# ADC.net
KiCad netlist of a schematic drawn in Altium Designer
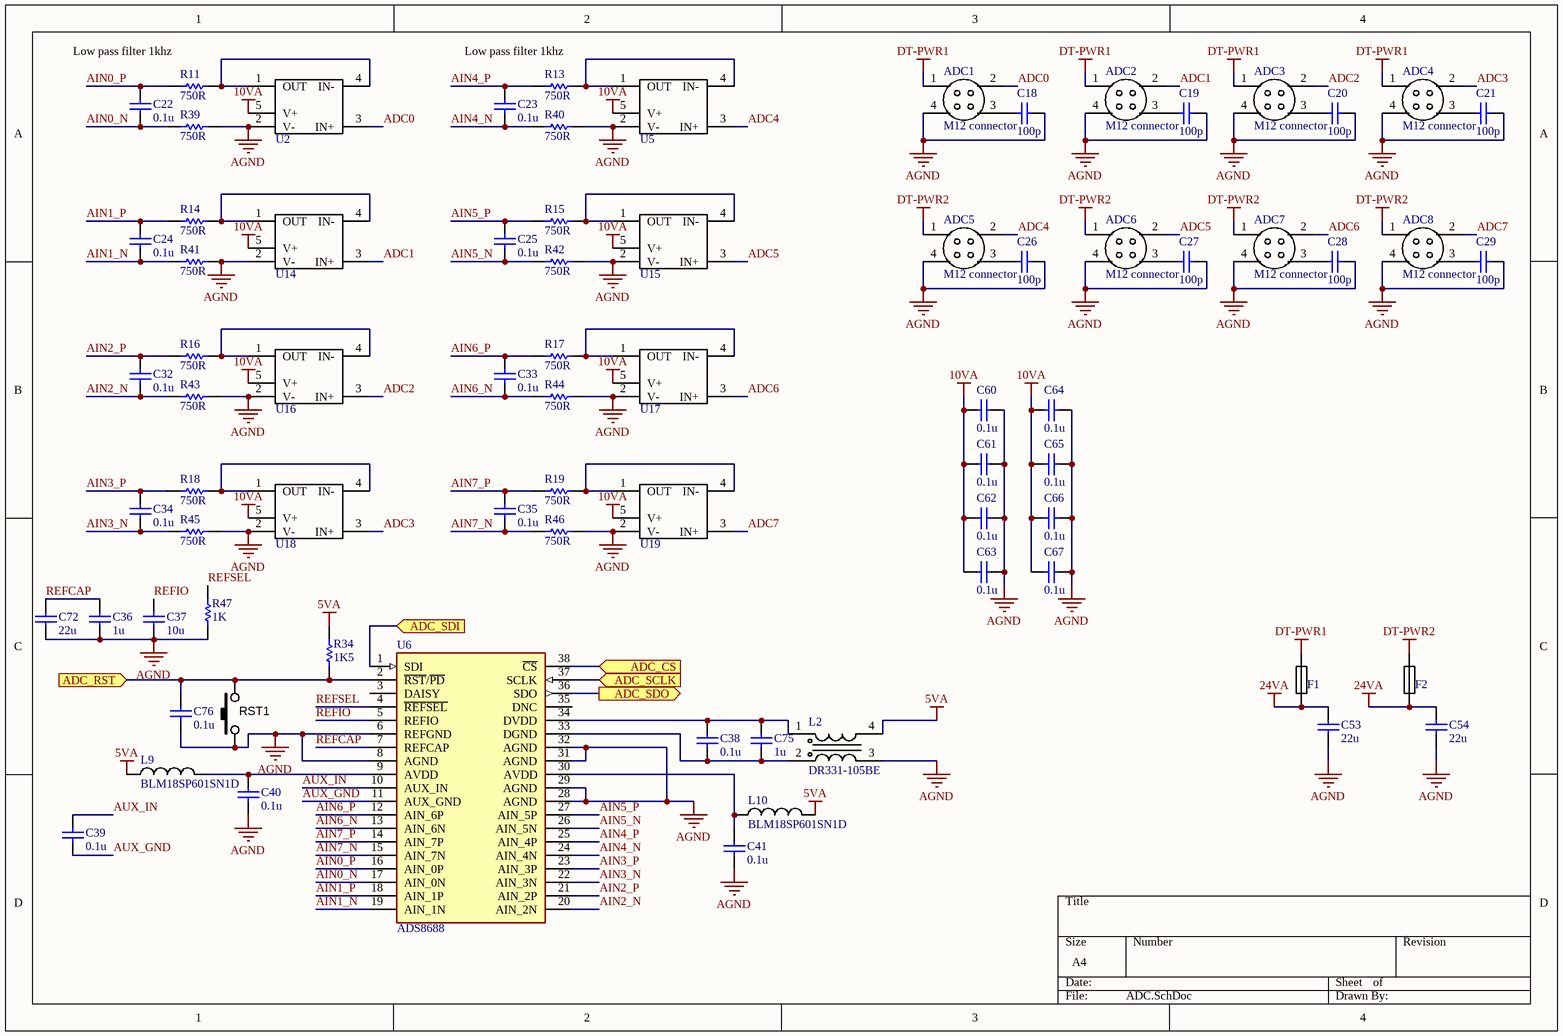
[diagram p0: ADC.SchDoc]

(export (version "E")
  (design (tool "Eeschema 10.0.6"))
  (components
    (comp (ref "ADC1")
      (value "M12 connector")
      (footprint "GX12_PCB_Mount")
      (description "M12 connect with 4 pin, current 4A per terminal")
      (libsource (lib "IOBoard") (part "M12_connector"))
    )
    (comp (ref "ADC2")
      (value "M12 connector")
      (footprint "GX12_PCB_Mount")
      (description "M12 connect with 4 pin, current 4A per terminal")
      (libsource (lib "IOBoard") (part "M12_connector"))
    )
    (comp (ref "ADC3")
      (value "M12 connector")
      (footprint "GX12_PCB_Mount")
      (description "M12 connect with 4 pin, current 4A per terminal")
      (libsource (lib "IOBoard") (part "M12_connector"))
    )
    (comp (ref "ADC4")
      (value "M12 connector")
      (footprint "GX12_PCB_Mount")
      (description "M12 connect with 4 pin, current 4A per terminal")
      (libsource (lib "IOBoard") (part "M12_connector"))
    )
    (comp (ref "ADC5")
      (value "M12 connector")
      (footprint "GX12_PCB_Mount")
      (description "M12 connect with 4 pin, current 4A per terminal")
      (libsource (lib "IOBoard") (part "M12_connector"))
    )
    (comp (ref "ADC6")
      (value "M12 connector")
      (footprint "GX12_PCB_Mount")
      (description "M12 connect with 4 pin, current 4A per terminal")
      (libsource (lib "IOBoard") (part "M12_connector"))
    )
    (comp (ref "ADC7")
      (value "M12 connector")
      (footprint "GX12_PCB_Mount")
      (description "M12 connect with 4 pin, current 4A per terminal")
      (libsource (lib "IOBoard") (part "M12_connector"))
    )
    (comp (ref "ADC8")
      (value "M12 connector")
      (footprint "GX12_PCB_Mount")
      (description "M12 connect with 4 pin, current 4A per terminal")
      (libsource (lib "IOBoard") (part "M12_connector"))
    )
    (comp (ref "C18")
      (value "100p")
      (footprint "CAPC1608X90N")
      (description "Capacitor")
      (fields (field (name "Comment") "Cap") (field (name "PUBLISHER") "Altium Limited"))
      (libsource (lib "IOBoard_Low") (part "Cap"))
    )
    (comp (ref "C19")
      (value "100p")
      (footprint "CAPC1608X90N")
      (description "Capacitor")
      (fields (field (name "Comment") "Cap") (field (name "PUBLISHER") "Altium Limited"))
      (libsource (lib "IOBoard_Low") (part "Cap"))
    )
    (comp (ref "C20")
      (value "100p")
      (footprint "CAPC1608X90N")
      (description "Capacitor")
      (fields (field (name "Comment") "Cap") (field (name "PUBLISHER") "Altium Limited"))
      (libsource (lib "IOBoard_Low") (part "Cap"))
    )
    (comp (ref "C21")
      (value "100p")
      (footprint "CAPC1608X90N")
      (description "Capacitor")
      (fields (field (name "Comment") "Cap") (field (name "PUBLISHER") "Altium Limited"))
      (libsource (lib "IOBoard_Low") (part "Cap"))
    )
    (comp (ref "C22")
      (value "0.1u")
      (footprint "CAPC1608X90N")
      (description "Capacitor")
      (fields (field (name "Comment") "Cap") (field (name "PUBLISHER") "Altium Limited"))
      (libsource (lib "IOBoard_Low") (part "Cap"))
    )
    (comp (ref "C23")
      (value "0.1u")
      (footprint "CAPC1608X90N")
      (description "Capacitor")
      (fields (field (name "Comment") "Cap") (field (name "PUBLISHER") "Altium Limited"))
      (libsource (lib "IOBoard_Low") (part "Cap"))
    )
    (comp (ref "C24")
      (value "0.1u")
      (footprint "CAPC1608X90N")
      (description "Capacitor")
      (fields (field (name "Comment") "Cap") (field (name "PUBLISHER") "Altium Limited"))
      (libsource (lib "IOBoard_Low") (part "Cap"))
    )
    (comp (ref "C25")
      (value "0.1u")
      (footprint "CAPC1608X90N")
      (description "Capacitor")
      (fields (field (name "Comment") "Cap") (field (name "PUBLISHER") "Altium Limited"))
      (libsource (lib "IOBoard_Low") (part "Cap"))
    )
    (comp (ref "C26")
      (value "100p")
      (footprint "CAPC1608X90N")
      (description "Capacitor")
      (fields (field (name "Comment") "Cap") (field (name "PUBLISHER") "Altium Limited"))
      (libsource (lib "IOBoard_Low") (part "Cap"))
    )
    (comp (ref "C27")
      (value "100p")
      (footprint "CAPC1608X90N")
      (description "Capacitor")
      (fields (field (name "Comment") "Cap") (field (name "PUBLISHER") "Altium Limited"))
      (libsource (lib "IOBoard_Low") (part "Cap"))
    )
    (comp (ref "C28")
      (value "100p")
      (footprint "CAPC1608X90N")
      (description "Capacitor")
      (fields (field (name "Comment") "Cap") (field (name "PUBLISHER") "Altium Limited"))
      (libsource (lib "IOBoard_Low") (part "Cap"))
    )
    (comp (ref "C29")
      (value "100p")
      (footprint "CAPC1608X90N")
      (description "Capacitor")
      (fields (field (name "Comment") "Cap") (field (name "PUBLISHER") "Altium Limited"))
      (libsource (lib "IOBoard_Low") (part "Cap"))
    )
    (comp (ref "C32")
      (value "0.1u")
      (footprint "CAPC1608X90N")
      (description "Capacitor")
      (fields (field (name "Comment") "Cap") (field (name "PUBLISHER") "Altium Limited"))
      (libsource (lib "IOBoard_Low") (part "Cap"))
    )
    (comp (ref "C33")
      (value "0.1u")
      (footprint "CAPC1608X90N")
      (description "Capacitor")
      (fields (field (name "Comment") "Cap") (field (name "PUBLISHER") "Altium Limited"))
      (libsource (lib "IOBoard_Low") (part "Cap"))
    )
    (comp (ref "C34")
      (value "0.1u")
      (footprint "CAPC1608X90N")
      (description "Capacitor")
      (fields (field (name "Comment") "Cap") (field (name "PUBLISHER") "Altium Limited"))
      (libsource (lib "IOBoard_Low") (part "Cap"))
    )
    (comp (ref "C35")
      (value "0.1u")
      (footprint "CAPC1608X90N")
      (description "Capacitor")
      (fields (field (name "Comment") "Cap") (field (name "PUBLISHER") "Altium Limited"))
      (libsource (lib "IOBoard_Low") (part "Cap"))
    )
    (comp (ref "C36")
      (value "1u")
      (footprint "CAPC1608X90N")
      (description "Capacitor")
      (fields (field (name "Comment") "Cap") (field (name "PUBLISHER") "Altium Limited"))
      (libsource (lib "IOBoard_Low") (part "Cap"))
    )
    (comp (ref "C37")
      (value "10u")
      (footprint "CAPC1608X90N")
      (description "Capacitor")
      (fields (field (name "Comment") "Cap") (field (name "PUBLISHER") "Altium Limited"))
      (libsource (lib "IOBoard_Low") (part "Cap"))
    )
    (comp (ref "C38")
      (value "0.1u")
      (footprint "CAPC1608X90N")
      (description "Capacitor")
      (fields (field (name "Comment") "Cap") (field (name "PUBLISHER") "Altium Limited"))
      (libsource (lib "IOBoard_Low") (part "Cap"))
    )
    (comp (ref "C39")
      (value "0.1u")
      (footprint "CAPC1608X90N")
      (description "Capacitor")
      (fields (field (name "Comment") "Cap") (field (name "PUBLISHER") "Altium Limited"))
      (libsource (lib "IOBoard_Low") (part "Cap"))
    )
    (comp (ref "C40")
      (value "0.1u")
      (footprint "CAPC1608X90N")
      (description "Capacitor")
      (fields (field (name "Comment") "Cap") (field (name "PUBLISHER") "Altium Limited"))
      (libsource (lib "IOBoard_Low") (part "Cap"))
    )
    (comp (ref "C41")
      (value "0.1u")
      (footprint "CAPC1608X90N")
      (description "Capacitor")
      (fields (field (name "Comment") "Cap") (field (name "PUBLISHER") "Altium Limited"))
      (libsource (lib "IOBoard_Low") (part "Cap"))
    )
    (comp (ref "C53")
      (value "22u")
      (footprint "CAPC2012X135N")
      (description "Capacitor")
      (fields (field (name "Comment") "Cap") (field (name "PUBLISHER") "Altium Limited"))
      (libsource (lib "IOBoard_Low") (part "Cap"))
    )
    (comp (ref "C54")
      (value "22u")
      (footprint "CAPC2012X135N")
      (description "Capacitor")
      (fields (field (name "Comment") "Cap") (field (name "PUBLISHER") "Altium Limited"))
      (libsource (lib "IOBoard_Low") (part "Cap"))
    )
    (comp (ref "C60")
      (value "0.1u")
      (footprint "CAPC1608X90N")
      (description "Capacitor")
      (fields (field (name "Comment") "Cap") (field (name "PUBLISHER") "Altium Limited"))
      (libsource (lib "IOBoard_Low") (part "Cap"))
    )
    (comp (ref "C61")
      (value "0.1u")
      (footprint "CAPC1608X90N")
      (description "Capacitor")
      (fields (field (name "Comment") "Cap") (field (name "PUBLISHER") "Altium Limited"))
      (libsource (lib "IOBoard_Low") (part "Cap"))
    )
    (comp (ref "C62")
      (value "0.1u")
      (footprint "CAPC1608X90N")
      (description "Capacitor")
      (fields (field (name "Comment") "Cap") (field (name "PUBLISHER") "Altium Limited"))
      (libsource (lib "IOBoard_Low") (part "Cap"))
    )
    (comp (ref "C63")
      (value "0.1u")
      (footprint "CAPC1608X90N")
      (description "Capacitor")
      (fields (field (name "Comment") "Cap") (field (name "PUBLISHER") "Altium Limited"))
      (libsource (lib "IOBoard_Low") (part "Cap"))
    )
    (comp (ref "C64")
      (value "0.1u")
      (footprint "CAPC1608X90N")
      (description "Capacitor")
      (fields (field (name "Comment") "Cap") (field (name "PUBLISHER") "Altium Limited"))
      (libsource (lib "IOBoard_Low") (part "Cap"))
    )
    (comp (ref "C65")
      (value "0.1u")
      (footprint "CAPC1608X90N")
      (description "Capacitor")
      (fields (field (name "Comment") "Cap") (field (name "PUBLISHER") "Altium Limited"))
      (libsource (lib "IOBoard_Low") (part "Cap"))
    )
    (comp (ref "C66")
      (value "0.1u")
      (footprint "CAPC1608X90N")
      (description "Capacitor")
      (fields (field (name "Comment") "Cap") (field (name "PUBLISHER") "Altium Limited"))
      (libsource (lib "IOBoard_Low") (part "Cap"))
    )
    (comp (ref "C67")
      (value "0.1u")
      (footprint "CAPC1608X90N")
      (description "Capacitor")
      (fields (field (name "Comment") "Cap") (field (name "PUBLISHER") "Altium Limited"))
      (libsource (lib "IOBoard_Low") (part "Cap"))
    )
    (comp (ref "C72")
      (value "22u")
      (footprint "CAPC2012X135N")
      (description "Capacitor")
      (fields (field (name "Comment") "Cap") (field (name "PUBLISHER") "Altium Limited"))
      (libsource (lib "IOBoard_Low") (part "Cap"))
    )
    (comp (ref "C75")
      (value "1u")
      (footprint "CAPC1608X90N")
      (description "Capacitor")
      (fields (field (name "Comment") "Cap") (field (name "PUBLISHER") "Altium Limited"))
      (libsource (lib "IOBoard_Low") (part "Cap"))
    )
    (comp (ref "C76")
      (value "0.1u")
      (footprint "CAPC1608X90N")
      (description "Capacitor")
      (fields (field (name "Comment") "Cap") (field (name "PUBLISHER") "Altium Limited"))
      (libsource (lib "IOBoard_Low") (part "Cap"))
    )
    (comp (ref "F1")
      (value "MFU0805FF00500P100")
      (footprint "RESC2012X70N")
      (description "fuse 32V 0.5A")
      (libsource (lib "IOBoard") (part "FUSE_32V_500MA_0805"))
    )
    (comp (ref "F2")
      (value "MFU0805FF00500P100")
      (footprint "RESC2012X70N")
      (description "fuse 32V 0.5A")
      (libsource (lib "IOBoard") (part "FUSE_32V_500MA_0805"))
    )
    (comp (ref "L2")
      (value "DR331-105BE")
      (footprint "DR331-105BE")
      (description "Common mode choke 1mH 0.5A")
      (libsource (lib "IOBoard_Low") (part "DR331-105BE"))
    )
    (comp (ref "L9")
      (value "BLM18SP601SN1D")
      (footprint "INDC1608N")
      (description "Ferritebead 1.5A, max 600ohm resistance")
      (libsource (lib "IOBoard") (part "INC_BLM18SP601SN1D"))
    )
    (comp (ref "L10")
      (value "BLM18SP601SN1D")
      (footprint "INDC1608N")
      (description "Ferritebead 1.5A, max 600ohm resistance")
      (libsource (lib "IOBoard") (part "INC_BLM18SP601SN1D"))
    )
    (comp (ref "R11")
      (value "750R")
      (footprint "RESC1608X55N")
      (description "Resistor")
      (fields (field (name "Comment") "Res1") (field (name "PUBLISHER") "Altium Limited"))
      (libsource (lib "IOBoard_Low") (part "Res1"))
    )
    (comp (ref "R13")
      (value "750R")
      (footprint "RESC1608X55N")
      (description "Resistor")
      (fields (field (name "Comment") "Res1") (field (name "PUBLISHER") "Altium Limited"))
      (libsource (lib "IOBoard_Low") (part "Res1"))
    )
    (comp (ref "R14")
      (value "750R")
      (footprint "RESC1608X55N")
      (description "Resistor")
      (fields (field (name "Comment") "Res1") (field (name "PUBLISHER") "Altium Limited"))
      (libsource (lib "IOBoard_Low") (part "Res1"))
    )
    (comp (ref "R15")
      (value "750R")
      (footprint "RESC1608X55N")
      (description "Resistor")
      (fields (field (name "Comment") "Res1") (field (name "PUBLISHER") "Altium Limited"))
      (libsource (lib "IOBoard_Low") (part "Res1"))
    )
    (comp (ref "R16")
      (value "750R")
      (footprint "RESC1608X55N")
      (description "Resistor")
      (fields (field (name "Comment") "Res1") (field (name "PUBLISHER") "Altium Limited"))
      (libsource (lib "IOBoard_Low") (part "Res1"))
    )
    (comp (ref "R17")
      (value "750R")
      (footprint "RESC1608X55N")
      (description "Resistor")
      (fields (field (name "Comment") "Res1") (field (name "PUBLISHER") "Altium Limited"))
      (libsource (lib "IOBoard_Low") (part "Res1"))
    )
    (comp (ref "R18")
      (value "750R")
      (footprint "RESC1608X55N")
      (description "Resistor")
      (fields (field (name "Comment") "Res1") (field (name "PUBLISHER") "Altium Limited"))
      (libsource (lib "IOBoard_Low") (part "Res1"))
    )
    (comp (ref "R19")
      (value "750R")
      (footprint "RESC1608X55N")
      (description "Resistor")
      (fields (field (name "Comment") "Res1") (field (name "PUBLISHER") "Altium Limited"))
      (libsource (lib "IOBoard_Low") (part "Res1"))
    )
    (comp (ref "R34")
      (value "1K5")
      (footprint "RESC1608X55N")
      (description "Resistor")
      (fields (field (name "Comment") "Res1") (field (name "PUBLISHER") "Altium Limited"))
      (libsource (lib "IOBoard_Low") (part "Res1"))
    )
    (comp (ref "R39")
      (value "750R")
      (footprint "RESC1608X55N")
      (description "Resistor")
      (fields (field (name "Comment") "Res1") (field (name "PUBLISHER") "Altium Limited"))
      (libsource (lib "IOBoard_Low") (part "Res1"))
    )
    (comp (ref "R40")
      (value "750R")
      (footprint "RESC1608X55N")
      (description "Resistor")
      (fields (field (name "Comment") "Res1") (field (name "PUBLISHER") "Altium Limited"))
      (libsource (lib "IOBoard_Low") (part "Res1"))
    )
    (comp (ref "R41")
      (value "750R")
      (footprint "RESC1608X55N")
      (description "Resistor")
      (fields (field (name "Comment") "Res1") (field (name "PUBLISHER") "Altium Limited"))
      (libsource (lib "IOBoard_Low") (part "Res1"))
    )
    (comp (ref "R42")
      (value "750R")
      (footprint "RESC1608X55N")
      (description "Resistor")
      (fields (field (name "Comment") "Res1") (field (name "PUBLISHER") "Altium Limited"))
      (libsource (lib "IOBoard_Low") (part "Res1"))
    )
    (comp (ref "R43")
      (value "750R")
      (footprint "RESC1608X55N")
      (description "Resistor")
      (fields (field (name "Comment") "Res1") (field (name "PUBLISHER") "Altium Limited"))
      (libsource (lib "IOBoard_Low") (part "Res1"))
    )
    (comp (ref "R44")
      (value "750R")
      (footprint "RESC1608X55N")
      (description "Resistor")
      (fields (field (name "Comment") "Res1") (field (name "PUBLISHER") "Altium Limited"))
      (libsource (lib "IOBoard_Low") (part "Res1"))
    )
    (comp (ref "R45")
      (value "750R")
      (footprint "RESC1608X55N")
      (description "Resistor")
      (fields (field (name "Comment") "Res1") (field (name "PUBLISHER") "Altium Limited"))
      (libsource (lib "IOBoard_Low") (part "Res1"))
    )
    (comp (ref "R46")
      (value "750R")
      (footprint "RESC1608X55N")
      (description "Resistor")
      (fields (field (name "Comment") "Res1") (field (name "PUBLISHER") "Altium Limited"))
      (libsource (lib "IOBoard_Low") (part "Res1"))
    )
    (comp (ref "R47")
      (value "1K")
      (footprint "RESC1608X55N")
      (description "Resistor")
      (fields (field (name "Comment") "Res1") (field (name "PUBLISHER") "Altium Limited"))
      (libsource (lib "IOBoard_Low") (part "Res1"))
    )
    (comp (ref "RST1")
      (value "SW_THT_PB_4.3mm")
      (footprint "TACT_SWT-SMD-4.4")
      (description "Switch, tact, 4.3mm stem")
      (libsource (lib "IOBoard") (part "SW_THT_PB_4.3mm"))
    )
    (comp (ref "U2")
      (value "OPA196")
      (footprint "SOT23-5")
      (description "operational amplifier 36V input")
      (libsource (lib "IOBoard_Low") (part "OPA196"))
    )
    (comp (ref "U5")
      (value "OPA196")
      (footprint "SOT23-5")
      (description "operational amplifier 36V input")
      (libsource (lib "IOBoard_Low") (part "OPA196"))
    )
    (comp (ref "U6")
      (value "ADS8688")
      (footprint "TSSOP38")
      (description "ADC 8 channel, 500KSPS")
      (libsource (lib "IOBoard") (part "ADS8688"))
    )
    (comp (ref "U14")
      (value "OPA196")
      (footprint "SOT23-5")
      (description "operational amplifier 36V input")
      (libsource (lib "IOBoard_Low") (part "OPA196"))
    )
    (comp (ref "U15")
      (value "OPA196")
      (footprint "SOT23-5")
      (description "operational amplifier 36V input")
      (libsource (lib "IOBoard_Low") (part "OPA196"))
    )
    (comp (ref "U16")
      (value "OPA196")
      (footprint "SOT23-5")
      (description "operational amplifier 36V input")
      (libsource (lib "IOBoard_Low") (part "OPA196"))
    )
    (comp (ref "U17")
      (value "OPA196")
      (footprint "SOT23-5")
      (description "operational amplifier 36V input")
      (libsource (lib "IOBoard_Low") (part "OPA196"))
    )
    (comp (ref "U18")
      (value "OPA196")
      (footprint "SOT23-5")
      (description "operational amplifier 36V input")
      (libsource (lib "IOBoard_Low") (part "OPA196"))
    )
    (comp (ref "U19")
      (value "OPA196")
      (footprint "SOT23-5")
      (description "operational amplifier 36V input")
      (libsource (lib "IOBoard_Low") (part "OPA196"))
    )
  )
  (nets
    (net (code "1") (name "/ADC0") (class "Default")
      (node (ref "ADC1") (pin "2") (pinfunction "2_2") (pintype "power_in"))
      (node (ref "U2") (pin "3") (pinfunction "IN+_3") (pintype "passive"))
    )
    (net (code "2") (name "/ADC1") (class "Default")
      (node (ref "ADC2") (pin "2") (pinfunction "2_2") (pintype "power_in"))
      (node (ref "U14") (pin "3") (pinfunction "IN+_3") (pintype "passive"))
    )
    (net (code "3") (name "/ADC2") (class "Default")
      (node (ref "ADC3") (pin "2") (pinfunction "2_2") (pintype "power_in"))
      (node (ref "U16") (pin "3") (pinfunction "IN+_3") (pintype "passive"))
    )
    (net (code "4") (name "/ADC3") (class "Default")
      (node (ref "ADC4") (pin "2") (pinfunction "2_2") (pintype "power_in"))
      (node (ref "U18") (pin "3") (pinfunction "IN+_3") (pintype "passive"))
    )
    (net (code "5") (name "/ADC4") (class "Default")
      (node (ref "ADC5") (pin "2") (pinfunction "2_2") (pintype "power_in"))
      (node (ref "U5") (pin "3") (pinfunction "IN+_3") (pintype "passive"))
    )
    (net (code "6") (name "/ADC5") (class "Default")
      (node (ref "ADC6") (pin "2") (pinfunction "2_2") (pintype "power_in"))
      (node (ref "U15") (pin "3") (pinfunction "IN+_3") (pintype "passive"))
    )
    (net (code "7") (name "/ADC6") (class "Default")
      (node (ref "ADC7") (pin "2") (pinfunction "2_2") (pintype "power_in"))
      (node (ref "U17") (pin "3") (pinfunction "IN+_3") (pintype "passive"))
    )
    (net (code "8") (name "/ADC7") (class "Default")
      (node (ref "ADC8") (pin "2") (pinfunction "2_2") (pintype "power_in"))
      (node (ref "U19") (pin "3") (pinfunction "IN+_3") (pintype "passive"))
    )
    (net (code "9") (name "/ADC_CS") (class "Default")
      (node (ref "U6") (pin "38") (pinfunction "~{CS}_38") (pintype "passive"))
    )
    (net (code "10") (name "/ADC_RST") (class "Default")
      (node (ref "C76") (pin "1") (pinfunction "1_1") (pintype "passive"))
      (node (ref "R34") (pin "1") (pinfunction "1_1") (pintype "passive"))
      (node (ref "RST1") (pin "2") (pintype "passive"))
      (node (ref "U6") (pin "2") (pinfunction "~{RST}/~{PD}_2") (pintype "passive"))
    )
    (net (code "11") (name "/ADC_SCLK") (class "Default")
      (node (ref "U6") (pin "37") (pinfunction "SCLK_37") (pintype "input"))
    )
    (net (code "12") (name "/ADC_SDI") (class "Default")
      (node (ref "U6") (pin "1") (pinfunction "SDI_1") (pintype "input"))
    )
    (net (code "13") (name "/ADC_SDO") (class "Default")
      (node (ref "U6") (pin "36") (pinfunction "SDO_36") (pintype "output"))
    )
    (net (code "14") (name "/AIN0_N") (class "Default")
      (node (ref "C22") (pin "1") (pinfunction "1_1") (pintype "passive"))
      (node (ref "R39") (pin "1") (pinfunction "1_1") (pintype "passive"))
      (node (ref "U6") (pin "17") (pinfunction "AIN_0N_17") (pintype "passive"))
    )
    (net (code "15") (name "/AIN0_P") (class "Default")
      (node (ref "C22") (pin "2") (pinfunction "2_2") (pintype "passive"))
      (node (ref "R11") (pin "1") (pinfunction "1_1") (pintype "passive"))
      (node (ref "U6") (pin "16") (pinfunction "AIN_0P_16") (pintype "passive"))
    )
    (net (code "16") (name "/AIN1_N") (class "Default")
      (node (ref "C24") (pin "1") (pinfunction "1_1") (pintype "passive"))
      (node (ref "R41") (pin "1") (pinfunction "1_1") (pintype "passive"))
      (node (ref "U6") (pin "19") (pinfunction "AIN_1N_19") (pintype "passive"))
    )
    (net (code "17") (name "/AIN1_P") (class "Default")
      (node (ref "C24") (pin "2") (pinfunction "2_2") (pintype "passive"))
      (node (ref "R14") (pin "1") (pinfunction "1_1") (pintype "passive"))
      (node (ref "U6") (pin "18") (pinfunction "AIN_1P_18") (pintype "passive"))
    )
    (net (code "18") (name "/AIN2_N") (class "Default")
      (node (ref "C32") (pin "1") (pinfunction "1_1") (pintype "passive"))
      (node (ref "R43") (pin "1") (pinfunction "1_1") (pintype "passive"))
      (node (ref "U6") (pin "20") (pinfunction "AIN_2N_20") (pintype "passive"))
    )
    (net (code "19") (name "/AIN2_P") (class "Default")
      (node (ref "C32") (pin "2") (pinfunction "2_2") (pintype "passive"))
      (node (ref "R16") (pin "1") (pinfunction "1_1") (pintype "passive"))
      (node (ref "U6") (pin "21") (pinfunction "AIN_2P_21") (pintype "passive"))
    )
    (net (code "20") (name "/AIN3_N") (class "Default")
      (node (ref "C34") (pin "1") (pinfunction "1_1") (pintype "passive"))
      (node (ref "R45") (pin "1") (pinfunction "1_1") (pintype "passive"))
      (node (ref "U6") (pin "22") (pinfunction "AIN_3N_22") (pintype "passive"))
    )
    (net (code "21") (name "/AIN3_P") (class "Default")
      (node (ref "C34") (pin "2") (pinfunction "2_2") (pintype "passive"))
      (node (ref "R18") (pin "1") (pinfunction "1_1") (pintype "passive"))
      (node (ref "U6") (pin "23") (pinfunction "AIN_3P_23") (pintype "passive"))
    )
    (net (code "22") (name "/AIN4_N") (class "Default")
      (node (ref "C23") (pin "1") (pinfunction "1_1") (pintype "passive"))
      (node (ref "R40") (pin "1") (pinfunction "1_1") (pintype "passive"))
      (node (ref "U6") (pin "24") (pinfunction "AIN_4N_24") (pintype "passive"))
    )
    (net (code "23") (name "/AIN4_P") (class "Default")
      (node (ref "C23") (pin "2") (pinfunction "2_2") (pintype "passive"))
      (node (ref "R13") (pin "1") (pinfunction "1_1") (pintype "passive"))
      (node (ref "U6") (pin "25") (pinfunction "AIN_4P_25") (pintype "passive"))
    )
    (net (code "24") (name "/AIN5_N") (class "Default")
      (node (ref "C25") (pin "1") (pinfunction "1_1") (pintype "passive"))
      (node (ref "R42") (pin "1") (pinfunction "1_1") (pintype "passive"))
      (node (ref "U6") (pin "26") (pinfunction "AIN_5N_26") (pintype "passive"))
    )
    (net (code "25") (name "/AIN5_P") (class "Default")
      (node (ref "C25") (pin "2") (pinfunction "2_2") (pintype "passive"))
      (node (ref "R15") (pin "1") (pinfunction "1_1") (pintype "passive"))
      (node (ref "U6") (pin "27") (pinfunction "AIN_5P_27") (pintype "passive"))
    )
    (net (code "26") (name "/AIN6_N") (class "Default")
      (node (ref "C33") (pin "1") (pinfunction "1_1") (pintype "passive"))
      (node (ref "R44") (pin "1") (pinfunction "1_1") (pintype "passive"))
      (node (ref "U6") (pin "13") (pinfunction "AIN_6N_13") (pintype "passive"))
    )
    (net (code "27") (name "/AIN6_P") (class "Default")
      (node (ref "C33") (pin "2") (pinfunction "2_2") (pintype "passive"))
      (node (ref "R17") (pin "1") (pinfunction "1_1") (pintype "passive"))
      (node (ref "U6") (pin "12") (pinfunction "AIN_6P_12") (pintype "passive"))
    )
    (net (code "28") (name "/AIN7_N") (class "Default")
      (node (ref "C35") (pin "1") (pinfunction "1_1") (pintype "passive"))
      (node (ref "R46") (pin "1") (pinfunction "1_1") (pintype "passive"))
      (node (ref "U6") (pin "15") (pinfunction "AIN_7N_15") (pintype "passive"))
    )
    (net (code "29") (name "/AIN7_P") (class "Default")
      (node (ref "C35") (pin "2") (pinfunction "2_2") (pintype "passive"))
      (node (ref "R19") (pin "1") (pinfunction "1_1") (pintype "passive"))
      (node (ref "U6") (pin "14") (pinfunction "AIN_7P_14") (pintype "passive"))
    )
    (net (code "30") (name "/AUX_GND") (class "Default")
      (node (ref "C39") (pin "1") (pinfunction "1_1") (pintype "passive"))
      (node (ref "U6") (pin "11") (pinfunction "AUX_GND_11") (pintype "passive"))
    )
    (net (code "31") (name "/AUX_IN") (class "Default")
      (node (ref "C39") (pin "2") (pinfunction "2_2") (pintype "passive"))
      (node (ref "U6") (pin "10") (pinfunction "AUX_IN_10") (pintype "passive"))
    )
    (net (code "32") (name "/REFCAP") (class "Default")
      (node (ref "C36") (pin "2") (pinfunction "2_2") (pintype "passive"))
      (node (ref "C72") (pin "2") (pinfunction "2_2") (pintype "passive"))
      (node (ref "U6") (pin "7") (pinfunction "REFCAP_7") (pintype "passive"))
    )
    (net (code "33") (name "/REFIO") (class "Default")
      (node (ref "C37") (pin "2") (pinfunction "2_2") (pintype "passive"))
      (node (ref "U6") (pin "5") (pinfunction "REFIO_5") (pintype "passive"))
    )
    (net (code "34") (name "/REFSEL") (class "Default")
      (node (ref "R47") (pin "2") (pinfunction "2_2") (pintype "passive"))
      (node (ref "U6") (pin "4") (pinfunction "~{REFSEL}_4") (pintype "passive"))
    )
    (net (code "35") (name "5VA") (class "Default")
      (node (ref "L10") (pin "2") (pinfunction "2_2") (pintype "passive"))
      (node (ref "L2") (pin "4") (pinfunction "VOUT+_4") (pintype "power_in"))
      (node (ref "L9") (pin "1") (pinfunction "1_1") (pintype "passive"))
      (node (ref "R34") (pin "2") (pinfunction "2_2") (pintype "passive"))
    )
    (net (code "36") (name "10VA") (class "Default")
      (node (ref "C60") (pin "2") (pinfunction "2_2") (pintype "passive"))
      (node (ref "C61") (pin "2") (pinfunction "2_2") (pintype "passive"))
      (node (ref "C62") (pin "2") (pinfunction "2_2") (pintype "passive"))
      (node (ref "C63") (pin "2") (pinfunction "2_2") (pintype "passive"))
      (node (ref "C64") (pin "2") (pinfunction "2_2") (pintype "passive"))
      (node (ref "C65") (pin "2") (pinfunction "2_2") (pintype "passive"))
      (node (ref "C66") (pin "2") (pinfunction "2_2") (pintype "passive"))
      (node (ref "C67") (pin "2") (pinfunction "2_2") (pintype "passive"))
      (node (ref "U14") (pin "5") (pinfunction "V+_5") (pintype "power_in"))
      (node (ref "U15") (pin "5") (pinfunction "V+_5") (pintype "power_in"))
      (node (ref "U16") (pin "5") (pinfunction "V+_5") (pintype "power_in"))
      (node (ref "U17") (pin "5") (pinfunction "V+_5") (pintype "power_in"))
      (node (ref "U18") (pin "5") (pinfunction "V+_5") (pintype "power_in"))
      (node (ref "U19") (pin "5") (pinfunction "V+_5") (pintype "power_in"))
      (node (ref "U2") (pin "5") (pinfunction "V+_5") (pintype "power_in"))
      (node (ref "U5") (pin "5") (pinfunction "V+_5") (pintype "power_in"))
    )
    (net (code "37") (name "24VA") (class "Default")
      (node (ref "C53") (pin "2") (pinfunction "2_2") (pintype "passive"))
      (node (ref "C54") (pin "2") (pinfunction "2_2") (pintype "passive"))
      (node (ref "F1") (pin "1") (pintype "passive"))
      (node (ref "F2") (pin "1") (pintype "passive"))
    )
    (net (code "38") (name "AGND") (class "Default")
      (node (ref "ADC1") (pin "4") (pinfunction "4_4") (pintype "power_in"))
      (node (ref "ADC2") (pin "4") (pinfunction "4_4") (pintype "power_in"))
      (node (ref "ADC3") (pin "4") (pinfunction "4_4") (pintype "power_in"))
      (node (ref "ADC4") (pin "4") (pinfunction "4_4") (pintype "power_in"))
      (node (ref "ADC5") (pin "4") (pinfunction "4_4") (pintype "power_in"))
      (node (ref "ADC6") (pin "4") (pinfunction "4_4") (pintype "power_in"))
      (node (ref "ADC7") (pin "4") (pinfunction "4_4") (pintype "power_in"))
      (node (ref "ADC8") (pin "4") (pinfunction "4_4") (pintype "power_in"))
      (node (ref "C18") (pin "1") (pinfunction "1_1") (pintype "passive"))
      (node (ref "C19") (pin "1") (pinfunction "1_1") (pintype "passive"))
      (node (ref "C20") (pin "1") (pinfunction "1_1") (pintype "passive"))
      (node (ref "C21") (pin "1") (pinfunction "1_1") (pintype "passive"))
      (node (ref "C26") (pin "1") (pinfunction "1_1") (pintype "passive"))
      (node (ref "C27") (pin "1") (pinfunction "1_1") (pintype "passive"))
      (node (ref "C28") (pin "1") (pinfunction "1_1") (pintype "passive"))
      (node (ref "C29") (pin "1") (pinfunction "1_1") (pintype "passive"))
      (node (ref "C36") (pin "1") (pinfunction "1_1") (pintype "passive"))
      (node (ref "C37") (pin "1") (pinfunction "1_1") (pintype "passive"))
      (node (ref "C40") (pin "1") (pinfunction "1_1") (pintype "passive"))
      (node (ref "C41") (pin "1") (pinfunction "1_1") (pintype "passive"))
      (node (ref "C53") (pin "1") (pinfunction "1_1") (pintype "passive"))
      (node (ref "C54") (pin "1") (pinfunction "1_1") (pintype "passive"))
      (node (ref "C60") (pin "1") (pinfunction "1_1") (pintype "passive"))
      (node (ref "C61") (pin "1") (pinfunction "1_1") (pintype "passive"))
      (node (ref "C62") (pin "1") (pinfunction "1_1") (pintype "passive"))
      (node (ref "C63") (pin "1") (pinfunction "1_1") (pintype "passive"))
      (node (ref "C64") (pin "1") (pinfunction "1_1") (pintype "passive"))
      (node (ref "C65") (pin "1") (pinfunction "1_1") (pintype "passive"))
      (node (ref "C66") (pin "1") (pinfunction "1_1") (pintype "passive"))
      (node (ref "C67") (pin "1") (pinfunction "1_1") (pintype "passive"))
      (node (ref "C72") (pin "1") (pinfunction "1_1") (pintype "passive"))
      (node (ref "C76") (pin "2") (pinfunction "2_2") (pintype "passive"))
      (node (ref "L2") (pin "3") (pinfunction "VOUT+_3") (pintype "power_in"))
      (node (ref "R39") (pin "2") (pinfunction "2_2") (pintype "passive"))
      (node (ref "R40") (pin "2") (pinfunction "2_2") (pintype "passive"))
      (node (ref "R41") (pin "2") (pinfunction "2_2") (pintype "passive"))
      (node (ref "R42") (pin "2") (pinfunction "2_2") (pintype "passive"))
      (node (ref "R43") (pin "2") (pinfunction "2_2") (pintype "passive"))
      (node (ref "R44") (pin "2") (pinfunction "2_2") (pintype "passive"))
      (node (ref "R45") (pin "2") (pinfunction "2_2") (pintype "passive"))
      (node (ref "R46") (pin "2") (pinfunction "2_2") (pintype "passive"))
      (node (ref "R47") (pin "1") (pinfunction "1_1") (pintype "passive"))
      (node (ref "RST1") (pin "1") (pintype "passive"))
      (node (ref "U14") (pin "2") (pinfunction "V-_2") (pintype "power_in"))
      (node (ref "U15") (pin "2") (pinfunction "V-_2") (pintype "power_in"))
      (node (ref "U16") (pin "2") (pinfunction "V-_2") (pintype "power_in"))
      (node (ref "U17") (pin "2") (pinfunction "V-_2") (pintype "power_in"))
      (node (ref "U18") (pin "2") (pinfunction "V-_2") (pintype "power_in"))
      (node (ref "U19") (pin "2") (pinfunction "V-_2") (pintype "power_in"))
      (node (ref "U2") (pin "2") (pinfunction "V-_2") (pintype "power_in"))
      (node (ref "U5") (pin "2") (pinfunction "V-_2") (pintype "power_in"))
      (node (ref "U6") (pin "28") (pinfunction "AGND_28") (pintype "power_in"))
      (node (ref "U6") (pin "29") (pinfunction "AGND_29") (pintype "power_in"))
      (node (ref "U6") (pin "31") (pinfunction "AGND_31") (pintype "power_in"))
      (node (ref "U6") (pin "32") (pinfunction "AGND_32") (pintype "power_in"))
      (node (ref "U6") (pin "6") (pinfunction "REFGND_6") (pintype "power_in"))
      (node (ref "U6") (pin "8") (pinfunction "AGND_8") (pintype "power_in"))
    )
    (net (code "39") (name "DT-PWR1") (class "Default")
      (node (ref "ADC1") (pin "1") (pinfunction "1_1") (pintype "power_in"))
      (node (ref "ADC2") (pin "1") (pinfunction "1_1") (pintype "power_in"))
      (node (ref "ADC3") (pin "1") (pinfunction "1_1") (pintype "power_in"))
      (node (ref "ADC4") (pin "1") (pinfunction "1_1") (pintype "power_in"))
      (node (ref "F1") (pin "2") (pintype "passive"))
    )
    (net (code "40") (name "DT-PWR2") (class "Default")
      (node (ref "ADC5") (pin "1") (pinfunction "1_1") (pintype "power_in"))
      (node (ref "ADC6") (pin "1") (pinfunction "1_1") (pintype "power_in"))
      (node (ref "ADC7") (pin "1") (pinfunction "1_1") (pintype "power_in"))
      (node (ref "ADC8") (pin "1") (pinfunction "1_1") (pintype "power_in"))
      (node (ref "F2") (pin "2") (pintype "passive"))
    )
    (net (code "41") (name "Net-(ADC1-Pad3)") (class "Default")
      (node (ref "ADC1") (pin "3") (pinfunction "3_3") (pintype "power_in"))
      (node (ref "C18") (pin "2") (pinfunction "2_2") (pintype "passive"))
    )
    (net (code "42") (name "Net-(ADC2-Pad3)") (class "Default")
      (node (ref "ADC2") (pin "3") (pinfunction "3_3") (pintype "power_in"))
      (node (ref "C19") (pin "2") (pinfunction "2_2") (pintype "passive"))
    )
    (net (code "43") (name "Net-(ADC3-Pad3)") (class "Default")
      (node (ref "ADC3") (pin "3") (pinfunction "3_3") (pintype "power_in"))
      (node (ref "C20") (pin "2") (pinfunction "2_2") (pintype "passive"))
    )
    (net (code "44") (name "Net-(ADC4-Pad3)") (class "Default")
      (node (ref "ADC4") (pin "3") (pinfunction "3_3") (pintype "power_in"))
      (node (ref "C21") (pin "2") (pinfunction "2_2") (pintype "passive"))
    )
    (net (code "45") (name "Net-(ADC5-Pad3)") (class "Default")
      (node (ref "ADC5") (pin "3") (pinfunction "3_3") (pintype "power_in"))
      (node (ref "C26") (pin "2") (pinfunction "2_2") (pintype "passive"))
    )
    (net (code "46") (name "Net-(ADC6-Pad3)") (class "Default")
      (node (ref "ADC6") (pin "3") (pinfunction "3_3") (pintype "power_in"))
      (node (ref "C27") (pin "2") (pinfunction "2_2") (pintype "passive"))
    )
    (net (code "47") (name "Net-(ADC7-Pad3)") (class "Default")
      (node (ref "ADC7") (pin "3") (pinfunction "3_3") (pintype "power_in"))
      (node (ref "C28") (pin "2") (pinfunction "2_2") (pintype "passive"))
    )
    (net (code "48") (name "Net-(ADC8-Pad3)") (class "Default")
      (node (ref "ADC8") (pin "3") (pinfunction "3_3") (pintype "power_in"))
      (node (ref "C29") (pin "2") (pinfunction "2_2") (pintype "passive"))
    )
    (net (code "49") (name "Net-(C40-Pad2)") (class "Default")
      (node (ref "C40") (pin "2") (pinfunction "2_2") (pintype "passive"))
      (node (ref "L9") (pin "2") (pinfunction "2_2") (pintype "passive"))
      (node (ref "U6") (pin "9") (pinfunction "AVDD_9") (pintype "power_in"))
    )
    (net (code "50") (name "Net-(C41-Pad2)") (class "Default")
      (node (ref "C41") (pin "2") (pinfunction "2_2") (pintype "passive"))
      (node (ref "L10") (pin "1") (pinfunction "1_1") (pintype "passive"))
      (node (ref "U6") (pin "30") (pinfunction "AVDD_30") (pintype "power_in"))
    )
    (net (code "51") (name "Net-(U2-IN-)") (class "Default")
      (node (ref "R11") (pin "2") (pinfunction "2_2") (pintype "passive"))
      (node (ref "U2") (pin "1") (pinfunction "OUT_1") (pintype "power_in"))
      (node (ref "U2") (pin "4") (pinfunction "IN-_4") (pintype "passive"))
    )
    (net (code "52") (name "Net-(U5-IN-)") (class "Default")
      (node (ref "R13") (pin "2") (pinfunction "2_2") (pintype "passive"))
      (node (ref "U5") (pin "1") (pinfunction "OUT_1") (pintype "power_in"))
      (node (ref "U5") (pin "4") (pinfunction "IN-_4") (pintype "passive"))
    )
    (net (code "53") (name "Net-(U6-DGND)") (class "Default")
      (node (ref "C38") (pin "1") (pinfunction "1_1") (pintype "passive"))
      (node (ref "C75") (pin "1") (pinfunction "1_1") (pintype "passive"))
      (node (ref "L2") (pin "2") (pinfunction "VOUT+_2") (pintype "power_in"))
      (node (ref "U6") (pin "33") (pinfunction "DGND_33") (pintype "power_in"))
    )
    (net (code "54") (name "Net-(U6-DVDD)") (class "Default")
      (node (ref "C38") (pin "2") (pinfunction "2_2") (pintype "passive"))
      (node (ref "C75") (pin "2") (pinfunction "2_2") (pintype "passive"))
      (node (ref "L2") (pin "1") (pinfunction "VOUT+_1") (pintype "power_in"))
      (node (ref "U6") (pin "34") (pinfunction "DVDD_34") (pintype "power_in"))
    )
    (net (code "55") (name "Net-(U14-IN-)") (class "Default")
      (node (ref "R14") (pin "2") (pinfunction "2_2") (pintype "passive"))
      (node (ref "U14") (pin "1") (pinfunction "OUT_1") (pintype "power_in"))
      (node (ref "U14") (pin "4") (pinfunction "IN-_4") (pintype "passive"))
    )
    (net (code "56") (name "Net-(U15-IN-)") (class "Default")
      (node (ref "R15") (pin "2") (pinfunction "2_2") (pintype "passive"))
      (node (ref "U15") (pin "1") (pinfunction "OUT_1") (pintype "power_in"))
      (node (ref "U15") (pin "4") (pinfunction "IN-_4") (pintype "passive"))
    )
    (net (code "57") (name "Net-(U16-IN-)") (class "Default")
      (node (ref "R16") (pin "2") (pinfunction "2_2") (pintype "passive"))
      (node (ref "U16") (pin "1") (pinfunction "OUT_1") (pintype "power_in"))
      (node (ref "U16") (pin "4") (pinfunction "IN-_4") (pintype "passive"))
    )
    (net (code "58") (name "Net-(U17-IN-)") (class "Default")
      (node (ref "R17") (pin "2") (pinfunction "2_2") (pintype "passive"))
      (node (ref "U17") (pin "1") (pinfunction "OUT_1") (pintype "power_in"))
      (node (ref "U17") (pin "4") (pinfunction "IN-_4") (pintype "passive"))
    )
    (net (code "59") (name "Net-(U18-IN-)") (class "Default")
      (node (ref "R18") (pin "2") (pinfunction "2_2") (pintype "passive"))
      (node (ref "U18") (pin "1") (pinfunction "OUT_1") (pintype "power_in"))
      (node (ref "U18") (pin "4") (pinfunction "IN-_4") (pintype "passive"))
    )
    (net (code "60") (name "Net-(U19-IN-)") (class "Default")
      (node (ref "R19") (pin "2") (pinfunction "2_2") (pintype "passive"))
      (node (ref "U19") (pin "1") (pinfunction "OUT_1") (pintype "power_in"))
      (node (ref "U19") (pin "4") (pinfunction "IN-_4") (pintype "passive"))
    )
    (net (code "61") (name "unconnected-(U6-DAISY-Pad3)") (class "Default")
      (node (ref "U6") (pin "3") (pinfunction "DAISY_3") (pintype "passive"))
    )
    (net (code "62") (name "unconnected-(U6-DNC-Pad35)") (class "Default")
      (node (ref "U6") (pin "35") (pinfunction "DNC_35") (pintype "passive"))
    )
  )
)
